# Adafruit_Feather_Zero_BLE_rev_A.net
KiCad netlist of a schematic drawn in EAGLE
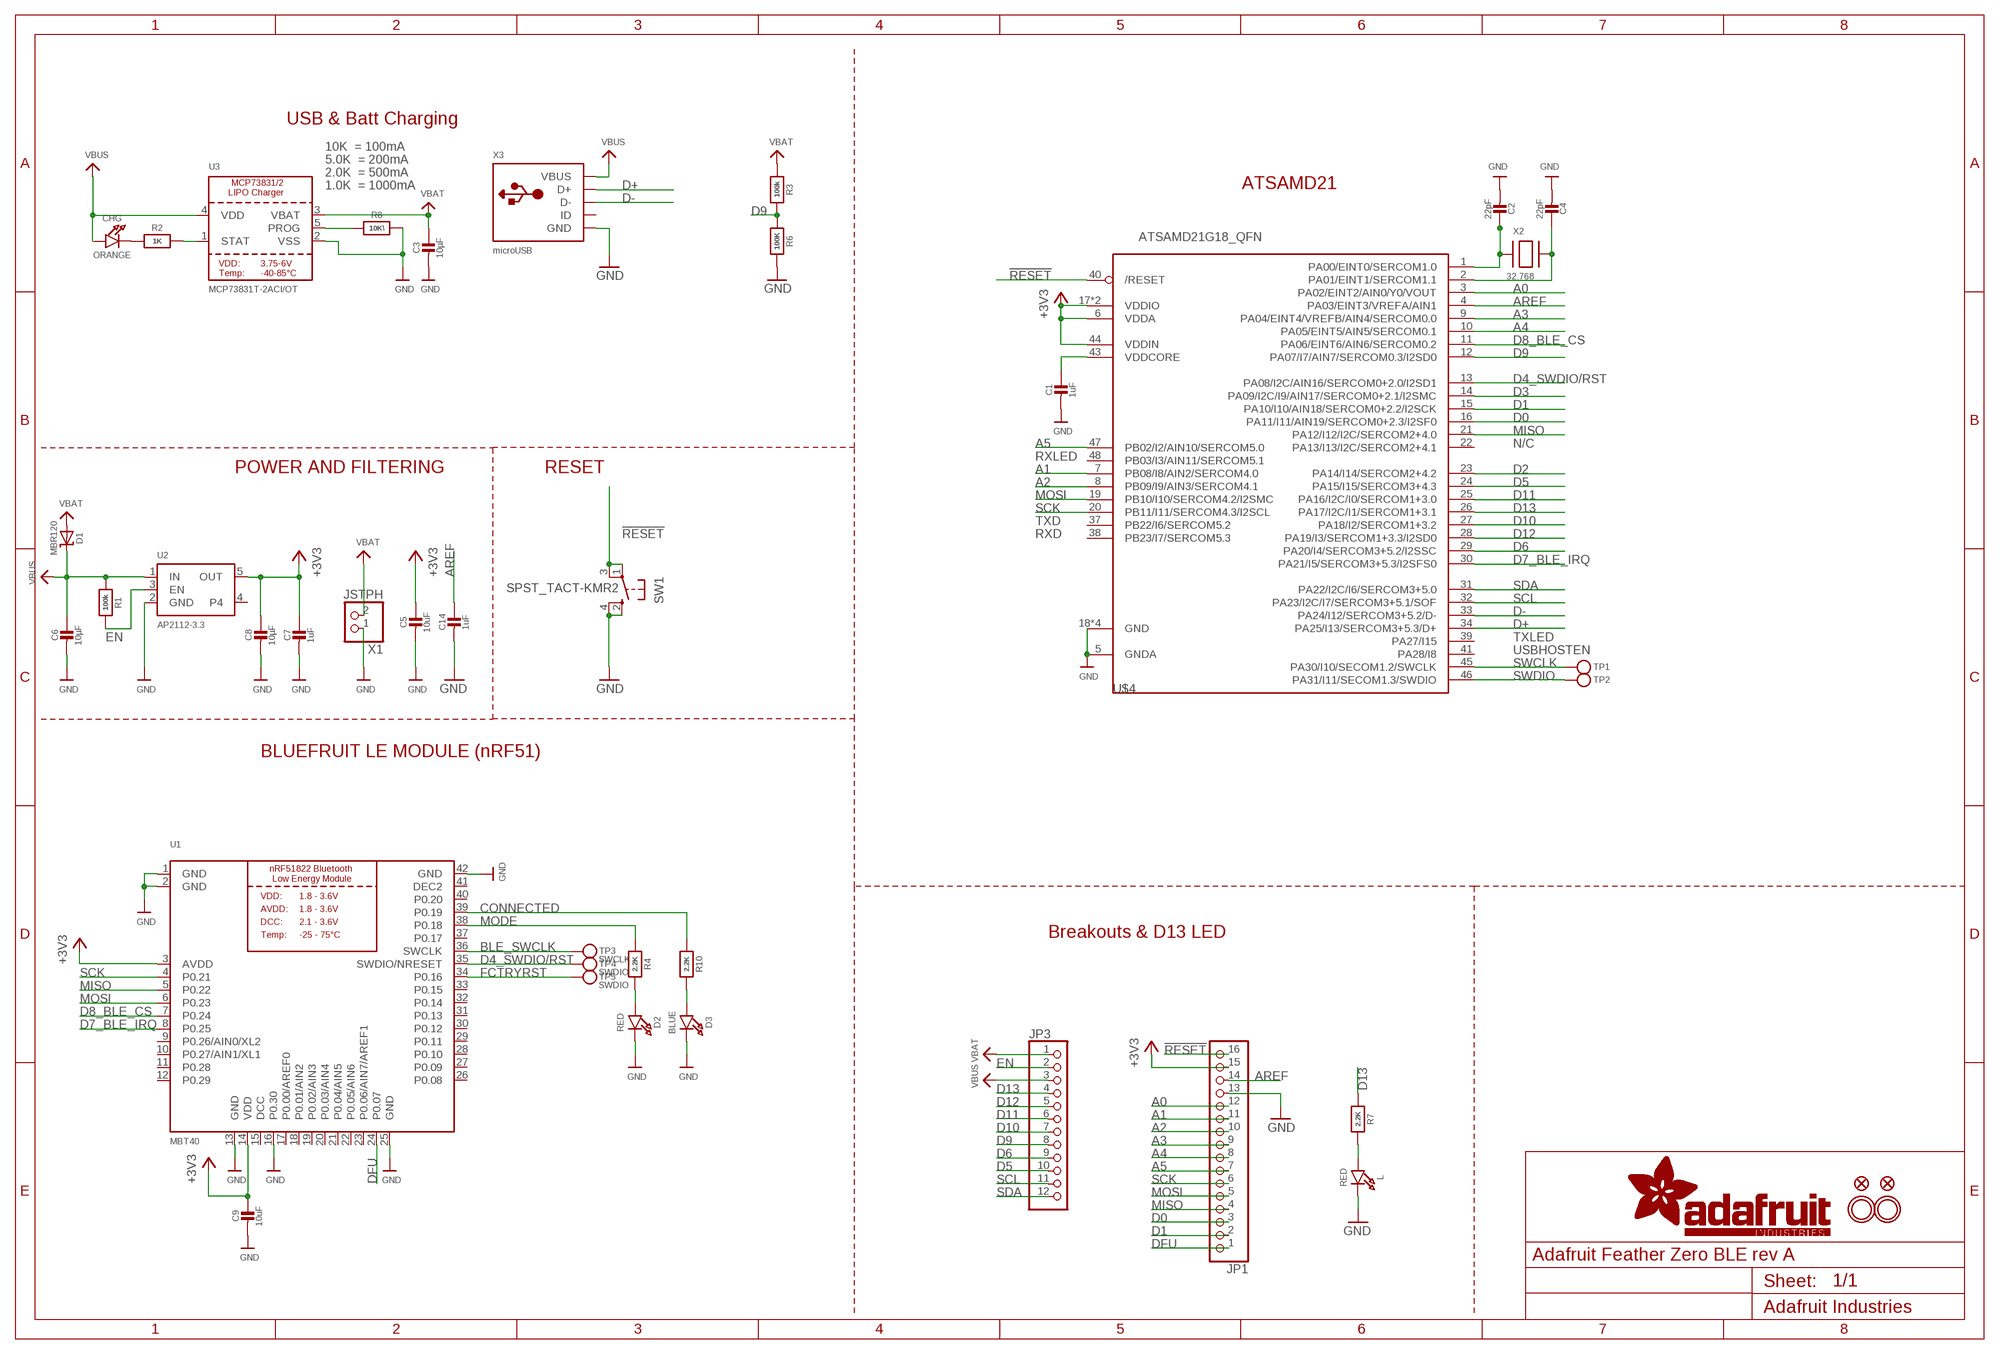
[diagram p0: schematic, sheet 1]

(export (version "E")
  (design (tool "Eeschema 10.0.6"))
  (components
    (comp (ref "C1")
      (value "1uF")
      (footprint "eagle-import:0603-NO")
      (libsource (lib "eagle-import") (part "CAP_CERAMIC0603_NO"))
    )
    (comp (ref "C2")
      (value "22pF")
      (footprint "eagle-import:0603-NO")
      (libsource (lib "eagle-import") (part "CAP_CERAMIC0603_NO"))
    )
    (comp (ref "C3")
      (value "10µF")
      (footprint "eagle-import:0805-NO")
      (libsource (lib "eagle-import") (part "CAP_CERAMIC0805-NOOUTLINE"))
    )
    (comp (ref "C4")
      (value "22pF")
      (footprint "eagle-import:0603-NO")
      (libsource (lib "eagle-import") (part "CAP_CERAMIC0603_NO"))
    )
    (comp (ref "C5")
      (value "10uF")
      (footprint "eagle-import:0805-NO")
      (libsource (lib "eagle-import") (part "CAP_CERAMIC0805-NOOUTLINE"))
    )
    (comp (ref "C6")
      (value "10µF")
      (footprint "eagle-import:0805-NO")
      (libsource (lib "eagle-import") (part "CAP_CERAMIC0805-NOOUTLINE"))
    )
    (comp (ref "C7")
      (value "1uF")
      (footprint "eagle-import:0603-NO")
      (libsource (lib "eagle-import") (part "CAP_CERAMIC0603_NO"))
    )
    (comp (ref "C8")
      (value "10µF")
      (footprint "eagle-import:0805-NO")
      (libsource (lib "eagle-import") (part "CAP_CERAMIC0805-NOOUTLINE"))
    )
    (comp (ref "C9")
      (value "10uF")
      (footprint "eagle-import:0805-NO")
      (libsource (lib "eagle-import") (part "CAP_CERAMIC0805-NOOUTLINE"))
    )
    (comp (ref "C14")
      (value "1uF")
      (footprint "eagle-import:0603-NO")
      (libsource (lib "eagle-import") (part "CAP_CERAMIC0603_NO"))
    )
    (comp (ref "CHG")
      (value "ORANGE")
      (footprint "eagle-import:CHIPLED_0805_NOOUTLINE")
      (libsource (lib "eagle-import") (part "LED0805_NOOUTLINE"))
    )
    (comp (ref "D1")
      (value "MBR120")
      (footprint "eagle-import:SOD-123")
      (libsource (lib "eagle-import") (part "DIODE-SCHOTTKYSOD-123"))
    )
    (comp (ref "D2")
      (value "RED")
      (footprint "eagle-import:CHIPLED_0805_NOOUTLINE")
      (libsource (lib "eagle-import") (part "LED0805_NOOUTLINE"))
    )
    (comp (ref "D3")
      (value "BLUE")
      (footprint "eagle-import:CHIPLED_0805_NOOUTLINE")
      (libsource (lib "eagle-import") (part "LED0805_NOOUTLINE"))
    )
    (comp (ref "JP1")
      (value "HEADER-1X16ROUND")
      (footprint "eagle-import:1X16_ROUND")
      (libsource (lib "eagle-import") (part "HEADER-1X16ROUND"))
    )
    (comp (ref "JP3")
      (value "HEADER-1X12")
      (footprint "eagle-import:1X12_ROUND")
      (libsource (lib "eagle-import") (part "HEADER-1X12"))
    )
    (comp (ref "L")
      (value "RED")
      (footprint "eagle-import:CHIPLED_0805_NOOUTLINE")
      (libsource (lib "eagle-import") (part "LED0805_NOOUTLINE"))
    )
    (comp (ref "R1")
      (value "100k")
      (footprint "eagle-import:0603-NO")
      (libsource (lib "eagle-import") (part "RESISTOR_0603_NOOUT"))
    )
    (comp (ref "R2")
      (value "1K")
      (footprint "eagle-import:0603-NO")
      (libsource (lib "eagle-import") (part "RESISTOR_0603_NOOUT"))
    )
    (comp (ref "R3")
      (value "100k")
      (footprint "eagle-import:0603-NO")
      (libsource (lib "eagle-import") (part "RESISTOR_0603_NOOUT"))
    )
    (comp (ref "R4")
      (value "2.2K")
      (footprint "eagle-import:0603-NO")
      (libsource (lib "eagle-import") (part "RESISTOR_0603_NOOUT"))
    )
    (comp (ref "R6")
      (value "100K")
      (footprint "eagle-import:0603-NO")
      (libsource (lib "eagle-import") (part "RESISTOR_0603_NOOUT"))
    )
    (comp (ref "R7")
      (value "2.2K")
      (footprint "eagle-import:0603-NO")
      (libsource (lib "eagle-import") (part "RESISTOR_0603_NOOUT"))
    )
    (comp (ref "R8")
      (value "10K\\")
      (footprint "eagle-import:0603-NO")
      (libsource (lib "eagle-import") (part "RESISTOR_0603_NOOUT"))
    )
    (comp (ref "R10")
      (value "2.2K")
      (footprint "eagle-import:0603-NO")
      (libsource (lib "eagle-import") (part "RESISTOR_0603_NOOUT"))
    )
    (comp (ref "SW1")
      (value "SPST_TACT-KMR2")
      (footprint "eagle-import:KMR2")
      (libsource (lib "eagle-import") (part "SPST_TACT-KMR2"))
    )
    (comp (ref "TP1")
      (value "TESTPOINTROUND1.5MM")
      (footprint "eagle-import:TESTPOINT_ROUND_1.5MM")
      (libsource (lib "eagle-import") (part "TESTPOINTROUND1.5MM"))
    )
    (comp (ref "TP2")
      (value "TESTPOINTROUND1.5MM")
      (footprint "eagle-import:TESTPOINT_ROUND_1.5MM")
      (libsource (lib "eagle-import") (part "TESTPOINTROUND1.5MM"))
    )
    (comp (ref "TP3")
      (value "SWCLK")
      (footprint "eagle-import:PAD-1.5X2.0")
      (libsource (lib "eagle-import") (part "TESTPOINT1.5X2.0MM_NOCREAM"))
    )
    (comp (ref "TP4")
      (value "SWDIO")
      (footprint "eagle-import:PAD-1.5X2.0")
      (libsource (lib "eagle-import") (part "TESTPOINT1.5X2.0MM_NOCREAM"))
    )
    (comp (ref "TP5")
      (value "SWDIO")
      (footprint "eagle-import:PAD-1.5X2.0")
      (libsource (lib "eagle-import") (part "TESTPOINT1.5X2.0MM_NOCREAM"))
    )
    (comp (ref "U$4")
      (value "ATSAMD21G18_QFN")
      (footprint "eagle-import:TQFN48_7MM")
      (libsource (lib "eagle-import") (part "ATSAMD21J_QFN"))
    )
    (comp (ref "U$31")
      (value "MOUNTINGHOLE2.5")
      (footprint "eagle-import:MOUNTINGHOLE_2.5_PLATED")
      (libsource (lib "eagle-import") (part "MOUNTINGHOLE2.5"))
    )
    (comp (ref "U$32")
      (value "MOUNTINGHOLE2.5")
      (footprint "eagle-import:MOUNTINGHOLE_2.5_PLATED")
      (libsource (lib "eagle-import") (part "MOUNTINGHOLE2.5"))
    )
    (comp (ref "U$34")
      (value "FIDUCIAL\"\"")
      (footprint "eagle-import:FIDUCIAL_1MM")
      (libsource (lib "eagle-import") (part "FIDUCIAL{dblquote}{dblquote}"))
    )
    (comp (ref "U$35")
      (value "FIDUCIAL\"\"")
      (footprint "eagle-import:FIDUCIAL_1MM")
      (libsource (lib "eagle-import") (part "FIDUCIAL{dblquote}{dblquote}"))
    )
    (comp (ref "U1")
      (value "MBT40")
      (footprint "eagle-import:BLE_MODULE_RAYTAC_MDBT40")
      (libsource (lib "eagle-import") (part "NRF51822_MODULE_MDBT40"))
    )
    (comp (ref "U2")
      (value "AP2112-3.3")
      (footprint "eagle-import:SOT23-5")
      (libsource (lib "eagle-import") (part "VREG_SOT23-5"))
    )
    (comp (ref "U3")
      (value "MCP73831T-2ACI/OT")
      (footprint "eagle-import:SOT23-5")
      (libsource (lib "eagle-import") (part "MCP73831/2"))
    )
    (comp (ref "X1")
      (value "JSTPH")
      (footprint "eagle-import:JSTPH2")
      (libsource (lib "eagle-import") (part "CON_JST_PH_2PIN"))
    )
    (comp (ref "X2")
      (value "32.768")
      (footprint "eagle-import:XTAL3215")
      (libsource (lib "eagle-import") (part "XTAL-3.2X1.5"))
    )
    (comp (ref "X3")
      (value "microUSB")
      (footprint "eagle-import:4UCONN_20329_V2")
      (libsource (lib "eagle-import") (part "USB_MICRO_20329_V2"))
    )
  )
  (nets
    (net (code "1") (name "+3V3") (class "Default")
      (node (ref "C5") (pin "1") (pinfunction "1_1") (pintype "passive"))
      (node (ref "C7") (pin "1") (pinfunction "1_1") (pintype "passive"))
      (node (ref "C8") (pin "1") (pinfunction "1_1") (pintype "passive"))
      (node (ref "C9") (pin "1") (pinfunction "1_1") (pintype "passive"))
      (node (ref "JP1") (pin "15") (pinfunction "15_15") (pintype "passive"))
      (node (ref "U$4") (pin "17") (pinfunction "VDDIO_17") (pintype "power_in"))
      (node (ref "U$4") (pin "36") (pinfunction "VDDIO_36") (pintype "power_in"))
      (node (ref "U$4") (pin "44") (pinfunction "VDDIN_44") (pintype "power_in"))
      (node (ref "U$4") (pin "6") (pinfunction "VDDA_6") (pintype "power_in"))
      (node (ref "U1") (pin "14") (pinfunction "VDD_14") (pintype "power_in"))
      (node (ref "U1") (pin "3") (pinfunction "AVDD_3") (pintype "power_in"))
      (node (ref "U2") (pin "5") (pinfunction "OUT_5") (pintype "power_in"))
    )
    (net (code "2") (name "/A0") (class "Default")
      (node (ref "JP1") (pin "12") (pinfunction "12_12") (pintype "passive"))
      (node (ref "U$4") (pin "3") (pinfunction "PA02/EINT2/AIN0/Y0/VOUT_3") (pintype "bidirectional"))
    )
    (net (code "3") (name "/A1") (class "Default")
      (node (ref "JP1") (pin "11") (pinfunction "11_11") (pintype "passive"))
      (node (ref "U$4") (pin "7") (pinfunction "PB08/I8/AIN2/SERCOM4.0_7") (pintype "bidirectional"))
    )
    (net (code "4") (name "/A2") (class "Default")
      (node (ref "JP1") (pin "10") (pinfunction "10_10") (pintype "passive"))
      (node (ref "U$4") (pin "8") (pinfunction "PB09/I9/AIN3/SERCOM4.1_8") (pintype "bidirectional"))
    )
    (net (code "5") (name "/A3") (class "Default")
      (node (ref "JP1") (pin "9") (pinfunction "9_9") (pintype "passive"))
      (node (ref "U$4") (pin "9") (pinfunction "PA04/EINT4/VREFB/AIN4/SERCOM0.0_9") (pintype "bidirectional"))
    )
    (net (code "6") (name "/A4") (class "Default")
      (node (ref "JP1") (pin "8") (pinfunction "8_8") (pintype "passive"))
      (node (ref "U$4") (pin "10") (pinfunction "PA05/EINT5/AIN5/SERCOM0.1_10") (pintype "bidirectional"))
    )
    (net (code "7") (name "/A5") (class "Default")
      (node (ref "JP1") (pin "7") (pinfunction "7_7") (pintype "passive"))
      (node (ref "U$4") (pin "47") (pinfunction "PB02/I2/AIN10/SERCOM5.0_47") (pintype "bidirectional"))
    )
    (net (code "8") (name "/AREF") (class "Default")
      (node (ref "C14") (pin "1") (pinfunction "1_1") (pintype "passive"))
      (node (ref "JP1") (pin "14") (pinfunction "14_14") (pintype "passive"))
      (node (ref "U$4") (pin "4") (pinfunction "PA03/EINT3/VREFA/AIN1_4") (pintype "bidirectional"))
    )
    (net (code "9") (name "/BLE_SWCLK") (class "Default")
      (node (ref "TP3") (pin "P$1") (pinfunction "P$1_P$1") (pintype "bidirectional"))
      (node (ref "U1") (pin "36") (pinfunction "SWCLK_36") (pintype "bidirectional"))
    )
    (net (code "10") (name "/CONNECTED") (class "Default")
      (node (ref "R10") (pin "1") (pinfunction "1_1") (pintype "passive"))
      (node (ref "U1") (pin "39") (pinfunction "P0.19_39") (pintype "bidirectional"))
    )
    (net (code "11") (name "/D+") (class "Default")
      (node (ref "U$4") (pin "34") (pinfunction "PA25/I13/SERCOM3+5.3/D+_34") (pintype "bidirectional"))
      (node (ref "X3") (pin "D+") (pinfunction "D+_D+") (pintype "bidirectional"))
    )
    (net (code "12") (name "/D-") (class "Default")
      (node (ref "U$4") (pin "33") (pinfunction "PA24/I12/SERCOM3+5.2/D-_33") (pintype "bidirectional"))
      (node (ref "X3") (pin "D-") (pinfunction "D-_D-") (pintype "bidirectional"))
    )
    (net (code "13") (name "/D0") (class "Default")
      (node (ref "JP1") (pin "3") (pinfunction "3_3") (pintype "passive"))
      (node (ref "U$4") (pin "16") (pinfunction "PA11/I11/AIN19/SERCOM0+2.3/I2SF0_16") (pintype "bidirectional"))
    )
    (net (code "14") (name "/D1") (class "Default")
      (node (ref "JP1") (pin "2") (pinfunction "2_2") (pintype "passive"))
      (node (ref "U$4") (pin "15") (pinfunction "PA10/I10/AIN18/SERCOM0+2.2/I2SCK_15") (pintype "bidirectional"))
    )
    (net (code "15") (name "/D2") (class "Default")
      (node (ref "U$4") (pin "23") (pinfunction "PA14/I14/SERCOM2+4.2_23") (pintype "bidirectional"))
    )
    (net (code "16") (name "/D3") (class "Default")
      (node (ref "U$4") (pin "14") (pinfunction "PA09/I2C/I9/AIN17/SERCOM0+2.1/I2SMC_14") (pintype "bidirectional"))
    )
    (net (code "17") (name "/D4_SWDIO{slash}RST") (class "Default")
      (node (ref "TP4") (pin "P$1") (pinfunction "P$1_P$1") (pintype "bidirectional"))
      (node (ref "U$4") (pin "13") (pinfunction "PA08/I2C/AIN16/SERCOM0+2.0/I2SD1_13") (pintype "bidirectional"))
      (node (ref "U1") (pin "35") (pinfunction "SWDIO/NRESET_35") (pintype "bidirectional"))
    )
    (net (code "18") (name "/D5") (class "Default")
      (node (ref "JP3") (pin "10") (pinfunction "10_10") (pintype "passive"))
      (node (ref "U$4") (pin "24") (pinfunction "PA15/I15/SERCOM3+4.3_24") (pintype "bidirectional"))
    )
    (net (code "19") (name "/D6") (class "Default")
      (node (ref "JP3") (pin "9") (pinfunction "9_9") (pintype "passive"))
      (node (ref "U$4") (pin "29") (pinfunction "PA20/I4/SERCOM3+5.2/I2SSC_29") (pintype "bidirectional"))
    )
    (net (code "20") (name "/D7_BLE_IRQ") (class "Default")
      (node (ref "U$4") (pin "30") (pinfunction "PA21/I5/SERCOM3+5.3/I2SFS0_30") (pintype "bidirectional"))
      (node (ref "U1") (pin "8") (pinfunction "P0.25_8") (pintype "bidirectional"))
    )
    (net (code "21") (name "/D8_BLE_CS") (class "Default")
      (node (ref "U$4") (pin "11") (pinfunction "PA06/EINT6/AIN6/SERCOM0.2_11") (pintype "bidirectional"))
      (node (ref "U1") (pin "7") (pinfunction "P0.24_7") (pintype "bidirectional"))
    )
    (net (code "22") (name "/D9") (class "Default")
      (node (ref "JP3") (pin "8") (pinfunction "8_8") (pintype "passive"))
      (node (ref "R3") (pin "2") (pinfunction "2_2") (pintype "passive"))
      (node (ref "R6") (pin "1") (pinfunction "1_1") (pintype "passive"))
      (node (ref "U$4") (pin "12") (pinfunction "PA07/I7/AIN7/SERCOM0.3/I2SD0_12") (pintype "bidirectional"))
    )
    (net (code "23") (name "/D10") (class "Default")
      (node (ref "JP3") (pin "7") (pinfunction "7_7") (pintype "passive"))
      (node (ref "U$4") (pin "27") (pinfunction "PA18/I2/SERCOM1+3.2_27") (pintype "bidirectional"))
    )
    (net (code "24") (name "/D11") (class "Default")
      (node (ref "JP3") (pin "6") (pinfunction "6_6") (pintype "passive"))
      (node (ref "U$4") (pin "25") (pinfunction "PA16/I2C/I0/SERCOM1+3.0_25") (pintype "bidirectional"))
    )
    (net (code "25") (name "/D12") (class "Default")
      (node (ref "JP3") (pin "5") (pinfunction "5_5") (pintype "passive"))
      (node (ref "U$4") (pin "28") (pinfunction "PA19/I3/SERCOM1+3.3/I2SD0_28") (pintype "bidirectional"))
    )
    (net (code "26") (name "/D13") (class "Default")
      (node (ref "JP3") (pin "4") (pinfunction "4_4") (pintype "passive"))
      (node (ref "R7") (pin "1") (pinfunction "1_1") (pintype "passive"))
      (node (ref "U$4") (pin "26") (pinfunction "PA17/I2C/I1/SERCOM1+3.1_26") (pintype "bidirectional"))
    )
    (net (code "27") (name "/DCC") (class "Default")
      (node (ref "U1") (pin "15") (pinfunction "DCC_15") (pintype "power_in"))
    )
    (net (code "28") (name "/DEC2") (class "Default")
      (node (ref "U1") (pin "41") (pinfunction "DEC2_41") (pintype "power_in"))
    )
    (net (code "29") (name "/DFU") (class "Default")
      (node (ref "JP1") (pin "1") (pinfunction "1_1") (pintype "passive"))
      (node (ref "U1") (pin "24") (pinfunction "P0.07_24") (pintype "bidirectional"))
    )
    (net (code "30") (name "/EN") (class "Default")
      (node (ref "JP3") (pin "2") (pinfunction "2_2") (pintype "passive"))
      (node (ref "R1") (pin "2") (pinfunction "2_2") (pintype "passive"))
      (node (ref "U2") (pin "3") (pinfunction "EN_3") (pintype "input"))
    )
    (net (code "31") (name "/FCTRYRST") (class "Default")
      (node (ref "TP5") (pin "P$1") (pinfunction "P$1_P$1") (pintype "bidirectional"))
      (node (ref "U1") (pin "34") (pinfunction "P0.16_34") (pintype "bidirectional"))
    )
    (net (code "32") (name "/MISO") (class "Default")
      (node (ref "JP1") (pin "4") (pinfunction "4_4") (pintype "passive"))
      (node (ref "U$4") (pin "21") (pinfunction "PA12/I12/I2C/SERCOM2+4.0_21") (pintype "bidirectional"))
      (node (ref "U1") (pin "5") (pinfunction "P0.22_5") (pintype "bidirectional"))
    )
    (net (code "33") (name "/MODE") (class "Default")
      (node (ref "R4") (pin "1") (pinfunction "1_1") (pintype "passive"))
      (node (ref "U1") (pin "38") (pinfunction "P0.18_38") (pintype "bidirectional"))
    )
    (net (code "34") (name "/MOSI") (class "Default")
      (node (ref "JP1") (pin "5") (pinfunction "5_5") (pintype "passive"))
      (node (ref "U$4") (pin "19") (pinfunction "PB10/I10/SERCOM4.2/I2SMC_19") (pintype "bidirectional"))
      (node (ref "U1") (pin "6") (pinfunction "P0.23_6") (pintype "bidirectional"))
    )
    (net (code "35") (name "/SCK") (class "Default")
      (node (ref "JP1") (pin "6") (pinfunction "6_6") (pintype "passive"))
      (node (ref "U$4") (pin "20") (pinfunction "PB11/I11/SERCOM4.3/I2SCL_20") (pintype "bidirectional"))
      (node (ref "U1") (pin "4") (pinfunction "P0.21_4") (pintype "bidirectional"))
    )
    (net (code "36") (name "/SCL") (class "Default")
      (node (ref "JP3") (pin "11") (pinfunction "11_11") (pintype "passive"))
      (node (ref "U$4") (pin "32") (pinfunction "PA23/I2C/I7/SERCOM3+5.1/SOF_32") (pintype "bidirectional"))
    )
    (net (code "37") (name "/SDA") (class "Default")
      (node (ref "JP3") (pin "12") (pinfunction "12_12") (pintype "passive"))
      (node (ref "U$4") (pin "31") (pinfunction "PA22/I2C/I6/SERCOM3+5.0_31") (pintype "bidirectional"))
    )
    (net (code "38") (name "/SWCLK") (class "Default")
      (node (ref "TP1") (pin "P$1") (pinfunction "P$1_P$1") (pintype "bidirectional"))
      (node (ref "U$4") (pin "45") (pinfunction "PA30/I10/SECOM1.2/SWCLK_45") (pintype "bidirectional"))
    )
    (net (code "39") (name "/SWDIO") (class "Default")
      (node (ref "TP2") (pin "P$1") (pinfunction "P$1_P$1") (pintype "bidirectional"))
      (node (ref "U$4") (pin "46") (pinfunction "PA31/I11/SECOM1.3/SWDIO_46") (pintype "bidirectional"))
    )
    (net (code "40") (name "/~{RESET}") (class "Default")
      (node (ref "JP1") (pin "16") (pinfunction "16_16") (pintype "passive"))
      (node (ref "SW1") (pin "1") (pinfunction "P_1") (pintype "passive"))
      (node (ref "SW1") (pin "3") (pinfunction "P1_3") (pintype "passive"))
      (node (ref "U$4") (pin "40") (pinfunction "/RESET_40") (pintype "bidirectional"))
    )
    (net (code "41") (name "GND") (class "Default")
      (node (ref "C1") (pin "2") (pinfunction "2_2") (pintype "passive"))
      (node (ref "C14") (pin "2") (pinfunction "2_2") (pintype "passive"))
      (node (ref "C2") (pin "2") (pinfunction "2_2") (pintype "passive"))
      (node (ref "C3") (pin "2") (pinfunction "2_2") (pintype "passive"))
      (node (ref "C4") (pin "2") (pinfunction "2_2") (pintype "passive"))
      (node (ref "C5") (pin "2") (pinfunction "2_2") (pintype "passive"))
      (node (ref "C6") (pin "2") (pinfunction "2_2") (pintype "passive"))
      (node (ref "C7") (pin "2") (pinfunction "2_2") (pintype "passive"))
      (node (ref "C8") (pin "2") (pinfunction "2_2") (pintype "passive"))
      (node (ref "C9") (pin "2") (pinfunction "2_2") (pintype "passive"))
      (node (ref "D2") (pin "C") (pinfunction "C_C") (pintype "passive"))
      (node (ref "D3") (pin "C") (pinfunction "C_C") (pintype "passive"))
      (node (ref "JP1") (pin "13") (pinfunction "13_13") (pintype "passive"))
      (node (ref "L") (pin "C") (pinfunction "C_C") (pintype "passive"))
      (node (ref "R6") (pin "2") (pinfunction "2_2") (pintype "passive"))
      (node (ref "R8") (pin "2") (pinfunction "2_2") (pintype "passive"))
      (node (ref "SW1") (pin "2") (pinfunction "S_2") (pintype "passive"))
      (node (ref "SW1") (pin "4") (pinfunction "S1_4") (pintype "passive"))
      (node (ref "U$4") (pin "18") (pinfunction "GND_18") (pintype "power_in"))
      (node (ref "U$4") (pin "35") (pinfunction "GND_35") (pintype "power_in"))
      (node (ref "U$4") (pin "42") (pinfunction "GND_42") (pintype "power_in"))
      (node (ref "U$4") (pin "5") (pinfunction "GNDA_5") (pintype "power_in"))
      (node (ref "U$4") (pin "THERMAL") (pinfunction "GND_THERMAL") (pintype "power_in"))
      (node (ref "U1") (pin "1") (pinfunction "GND_1") (pintype "power_in"))
      (node (ref "U1") (pin "13") (pinfunction "GND_13") (pintype "power_in"))
      (node (ref "U1") (pin "16") (pinfunction "P0.30_16") (pintype "bidirectional"))
      (node (ref "U1") (pin "2") (pinfunction "GND_2") (pintype "power_in"))
      (node (ref "U1") (pin "25") (pinfunction "GND_25") (pintype "power_in"))
      (node (ref "U1") (pin "42") (pinfunction "GND_42") (pintype "power_in"))
      (node (ref "U2") (pin "2") (pinfunction "GND_2") (pintype "power_in"))
      (node (ref "U3") (pin "2") (pinfunction "VSS_2") (pintype "power_in"))
      (node (ref "X1") (pin "1") (pinfunction "1_1") (pintype "passive"))
      (node (ref "X3") (pin "BASE@1") (pinfunction "GND_BASE@1") (pintype "power_in"))
      (node (ref "X3") (pin "BASE@2") (pinfunction "GND_BASE@2") (pintype "power_in"))
      (node (ref "X3") (pin "GND") (pinfunction "GND_GND") (pintype "power_in"))
      (node (ref "X3") (pin "SPRT@1") (pinfunction "GND_SPRT@1") (pintype "power_in"))
      (node (ref "X3") (pin "SPRT@2") (pinfunction "GND_SPRT@2") (pintype "power_in"))
      (node (ref "X3") (pin "SPRT@3") (pinfunction "GND_SPRT@3") (pintype "power_in"))
      (node (ref "X3") (pin "SPRT@4") (pinfunction "GND_SPRT@4") (pintype "power_in"))
    )
    (net (code "42") (name "Net-(CHG-PadC)") (class "Default")
      (node (ref "CHG") (pin "C") (pinfunction "C_C") (pintype "passive"))
      (node (ref "R2") (pin "1") (pinfunction "1_1") (pintype "passive"))
    )
    (net (code "43") (name "Net-(D2-PadA)") (class "Default")
      (node (ref "D2") (pin "A") (pinfunction "A_A") (pintype "passive"))
      (node (ref "R4") (pin "2") (pinfunction "2_2") (pintype "passive"))
    )
    (net (code "44") (name "Net-(D3-PadA)") (class "Default")
      (node (ref "D3") (pin "A") (pinfunction "A_A") (pintype "passive"))
      (node (ref "R10") (pin "2") (pinfunction "2_2") (pintype "passive"))
    )
    (net (code "45") (name "Net-(L-PadA)") (class "Default")
      (node (ref "L") (pin "A") (pinfunction "A_A") (pintype "passive"))
      (node (ref "R7") (pin "2") (pinfunction "2_2") (pintype "passive"))
    )
    (net (code "46") (name "Net-(U$4-PA00{slash}EINT0{slash}SERCOM1.0)") (class "Default")
      (node (ref "C2") (pin "1") (pinfunction "1_1") (pintype "passive"))
      (node (ref "U$4") (pin "1") (pinfunction "PA00/EINT0/SERCOM1.0_1") (pintype "bidirectional"))
      (node (ref "X2") (pin "P$1") (pinfunction "P$1_P$1") (pintype "bidirectional"))
    )
    (net (code "47") (name "Net-(U$4-PA01{slash}EINT1{slash}SERCOM1.1)") (class "Default")
      (node (ref "C4") (pin "1") (pinfunction "1_1") (pintype "passive"))
      (node (ref "U$4") (pin "2") (pinfunction "PA01/EINT1/SERCOM1.1_2") (pintype "bidirectional"))
      (node (ref "X2") (pin "P$2") (pinfunction "P$2_P$2") (pintype "bidirectional"))
    )
    (net (code "48") (name "Net-(U$4-VDDCORE)") (class "Default")
      (node (ref "C1") (pin "1") (pinfunction "1_1") (pintype "passive"))
      (node (ref "U$4") (pin "43") (pinfunction "VDDCORE_43") (pintype "power_in"))
    )
    (net (code "49") (name "Net-(U3-PROG)") (class "Default")
      (node (ref "R8") (pin "1") (pinfunction "1_1") (pintype "passive"))
      (node (ref "U3") (pin "5") (pinfunction "PROG_5") (pintype "input"))
    )
    (net (code "50") (name "Net-(U3-STAT)") (class "Default")
      (node (ref "R2") (pin "2") (pinfunction "2_2") (pintype "passive"))
      (node (ref "U3") (pin "1") (pinfunction "STAT_1") (pintype "output"))
    )
    (net (code "51") (name "VBAT") (class "Default")
      (node (ref "C3") (pin "1") (pinfunction "1_1") (pintype "passive"))
      (node (ref "D1") (pin "A") (pinfunction "A_A") (pintype "passive"))
      (node (ref "JP3") (pin "1") (pinfunction "1_1") (pintype "passive"))
      (node (ref "R3") (pin "1") (pinfunction "1_1") (pintype "passive"))
      (node (ref "U3") (pin "3") (pinfunction "VBAT_3") (pintype "power_in"))
      (node (ref "X1") (pin "2") (pinfunction "2_2") (pintype "passive"))
    )
    (net (code "52") (name "VBUS") (class "Default")
      (node (ref "C6") (pin "1") (pinfunction "1_1") (pintype "passive"))
      (node (ref "CHG") (pin "A") (pinfunction "A_A") (pintype "passive"))
      (node (ref "D1") (pin "C") (pinfunction "C_C") (pintype "passive"))
      (node (ref "JP3") (pin "3") (pinfunction "3_3") (pintype "passive"))
      (node (ref "R1") (pin "1") (pinfunction "1_1") (pintype "passive"))
      (node (ref "U2") (pin "1") (pinfunction "IN_1") (pintype "power_in"))
      (node (ref "U3") (pin "4") (pinfunction "VDD_4") (pintype "power_in"))
      (node (ref "X3") (pin "VBUS") (pinfunction "VBUS_VBUS") (pintype "power_in"))
    )
    (net (code "53") (name "unconnected-(U$4-PA13{slash}I13{slash}I2C{slash}SERCOM2+4.1-Pad22)") (class "Default")
      (node (ref "U$4") (pin "22") (pinfunction "PA13/I13/I2C/SERCOM2+4.1_22") (pintype "bidirectional"))
    )
    (net (code "54") (name "unconnected-(U$4-PA27{slash}I15-Pad39)") (class "Default")
      (node (ref "U$4") (pin "39") (pinfunction "PA27/I15_39") (pintype "bidirectional"))
    )
    (net (code "55") (name "unconnected-(U$4-PA28{slash}I8-Pad41)") (class "Default")
      (node (ref "U$4") (pin "41") (pinfunction "PA28/I8_41") (pintype "bidirectional"))
    )
    (net (code "56") (name "unconnected-(U$4-PB03{slash}I3{slash}AIN11{slash}SERCOM5.1-Pad48)") (class "Default")
      (node (ref "U$4") (pin "48") (pinfunction "PB03/I3/AIN11/SERCOM5.1_48") (pintype "bidirectional"))
    )
    (net (code "57") (name "unconnected-(U$4-PB22{slash}I6{slash}SERCOM5.2-Pad37)") (class "Default")
      (node (ref "U$4") (pin "37") (pinfunction "PB22/I6/SERCOM5.2_37") (pintype "bidirectional"))
    )
    (net (code "58") (name "unconnected-(U$4-PB23{slash}I7{slash}SERCOM5.3-Pad38)") (class "Default")
      (node (ref "U$4") (pin "38") (pinfunction "PB23/I7/SERCOM5.3_38") (pintype "bidirectional"))
    )
    (net (code "59") (name "unconnected-(U1-P0.00{slash}AREF0-Pad17)") (class "Default")
      (node (ref "U1") (pin "17") (pinfunction "P0.00/AREF0_17") (pintype "bidirectional"))
    )
    (net (code "60") (name "unconnected-(U1-P0.01{slash}AIN2-Pad18)") (class "Default")
      (node (ref "U1") (pin "18") (pinfunction "P0.01/AIN2_18") (pintype "bidirectional"))
    )
    (net (code "61") (name "unconnected-(U1-P0.02{slash}AIN3-Pad19)") (class "Default")
      (node (ref "U1") (pin "19") (pinfunction "P0.02/AIN3_19") (pintype "bidirectional"))
    )
    (net (code "62") (name "unconnected-(U1-P0.03{slash}AIN4-Pad20)") (class "Default")
      (node (ref "U1") (pin "20") (pinfunction "P0.03/AIN4_20") (pintype "bidirectional"))
    )
    (net (code "63") (name "unconnected-(U1-P0.04{slash}AIN5-Pad21)") (class "Default")
      (node (ref "U1") (pin "21") (pinfunction "P0.04/AIN5_21") (pintype "bidirectional"))
    )
    (net (code "64") (name "unconnected-(U1-P0.05{slash}AIN6-Pad22)") (class "Default")
      (node (ref "U1") (pin "22") (pinfunction "P0.05/AIN6_22") (pintype "bidirectional"))
    )
    (net (code "65") (name "unconnected-(U1-P0.06{slash}AIN7{slash}AREF1-Pad23)") (class "Default")
      (node (ref "U1") (pin "23") (pinfunction "P0.06/AIN7/AREF1_23") (pintype "bidirectional"))
    )
    (net (code "66") (name "unconnected-(U1-P0.08-Pad26)") (class "Default")
      (node (ref "U1") (pin "26") (pinfunction "P0.08_26") (pintype "bidirectional"))
    )
    (net (code "67") (name "unconnected-(U1-P0.09-Pad27)") (class "Default")
      (node (ref "U1") (pin "27") (pinfunction "P0.09_27") (pintype "bidirectional"))
    )
    (net (code "68") (name "unconnected-(U1-P0.10-Pad28)") (class "Default")
      (node (ref "U1") (pin "28") (pinfunction "P0.10_28") (pintype "bidirectional"))
    )
    (net (code "69") (name "unconnected-(U1-P0.11-Pad29)") (class "Default")
      (node (ref "U1") (pin "29") (pinfunction "P0.11_29") (pintype "bidirectional"))
    )
    (net (code "70") (name "unconnected-(U1-P0.12-Pad30)") (class "Default")
      (node (ref "U1") (pin "30") (pinfunction "P0.12_30") (pintype "bidirectional"))
    )
    (net (code "71") (name "unconnected-(U1-P0.13-Pad31)") (class "Default")
      (node (ref "U1") (pin "31") (pinfunction "P0.13_31") (pintype "bidirectional"))
    )
    (net (code "72") (name "unconnected-(U1-P0.14-Pad32)") (class "Default")
      (node (ref "U1") (pin "32") (pinfunction "P0.14_32") (pintype "bidirectional"))
    )
    (net (code "73") (name "unconnected-(U1-P0.15-Pad33)") (class "Default")
      (node (ref "U1") (pin "33") (pinfunction "P0.15_33") (pintype "bidirectional"))
    )
    (net (code "74") (name "unconnected-(U1-P0.17-Pad37)") (class "Default")
      (node (ref "U1") (pin "37") (pinfunction "P0.17_37") (pintype "bidirectional"))
    )
    (net (code "75") (name "unconnected-(U1-P0.20-Pad40)") (class "Default")
      (node (ref "U1") (pin "40") (pinfunction "P0.20_40") (pintype "bidirectional"))
    )
    (net (code "76") (name "unconnected-(U1-P0.26{slash}AIN0{slash}XL2-Pad9)") (class "Default")
      (node (ref "U1") (pin "9") (pinfunction "P0.26/AIN0/XL2_9") (pintype "bidirectional"))
    )
    (net (code "77") (name "unconnected-(U1-P0.27{slash}AIN1{slash}XL1-Pad10)") (class "Default")
      (node (ref "U1") (pin "10") (pinfunction "P0.27/AIN1/XL1_10") (pintype "bidirectional"))
    )
    (net (code "78") (name "unconnected-(U1-P0.28-Pad11)") (class "Default")
      (node (ref "U1") (pin "11") (pinfunction "P0.28_11") (pintype "bidirectional"))
    )
    (net (code "79") (name "unconnected-(U1-P0.29-Pad12)") (class "Default")
      (node (ref "U1") (pin "12") (pinfunction "P0.29_12") (pintype "bidirectional"))
    )
    (net (code "80") (name "unconnected-(U2-P4-Pad4)") (class "Default")
      (node (ref "U2") (pin "4") (pinfunction "P4_4") (pintype "bidirectional"))
    )
    (net (code "81") (name "unconnected-(X3-PadID)") (class "Default")
      (node (ref "X3") (pin "ID") (pinfunction "ID_ID") (pintype "bidirectional"))
    )
  )
)
